# Auth.net
KiCad netlist of a schematic drawn in Altium Designer
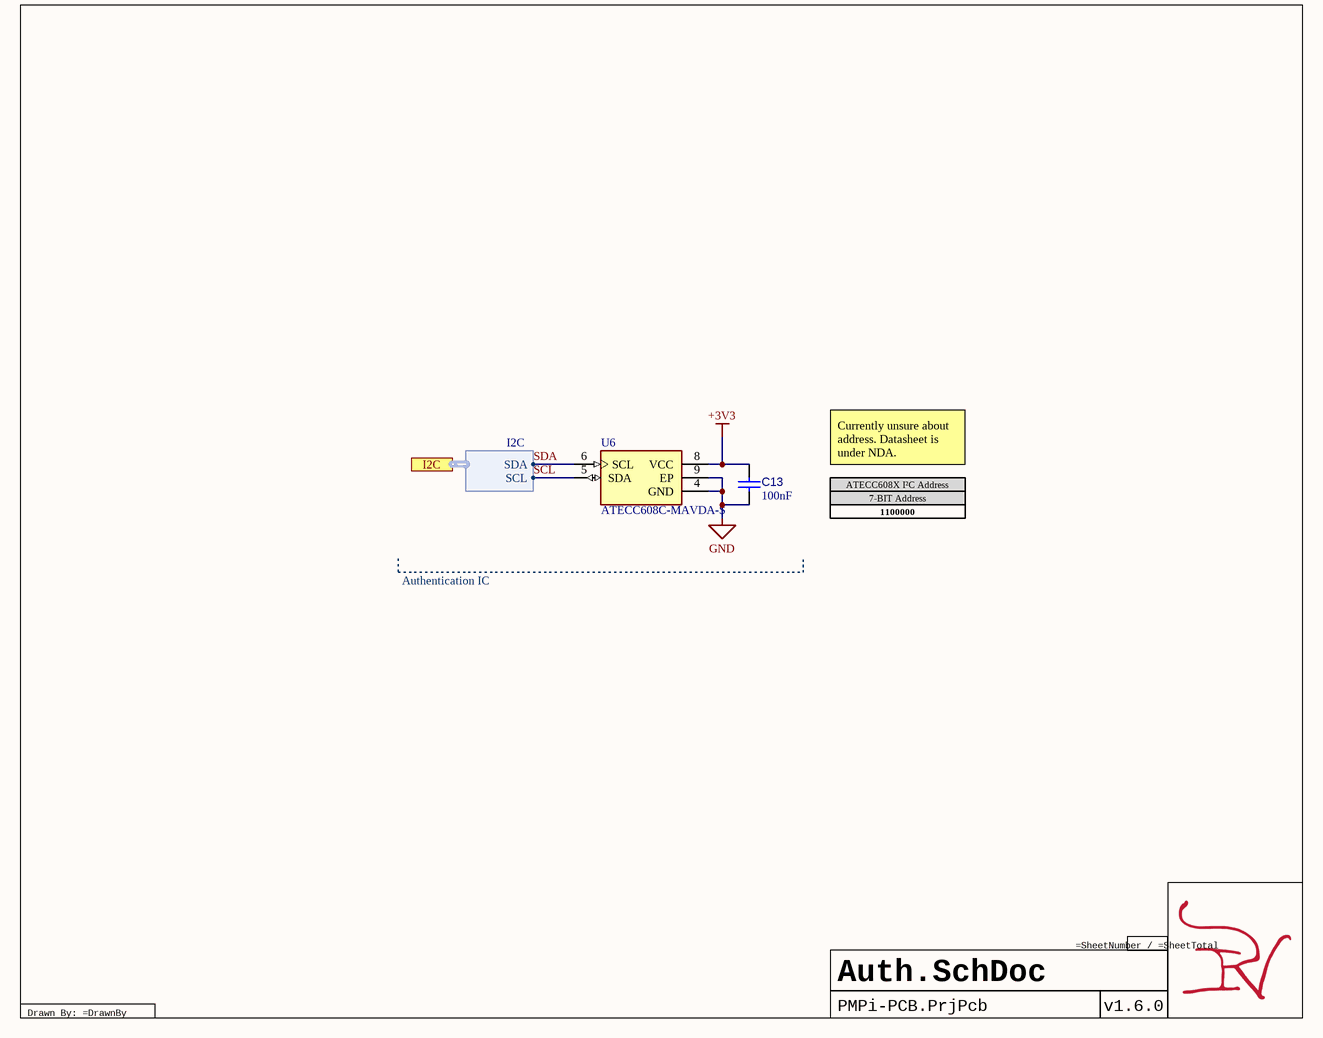
[diagram p0: Auth.SchDoc]

(export (version "E")
  (design (tool "Eeschema 10.0.6"))
  (components
    (comp (ref "C13")
      (value "100nF")
      (footprint "CAP 0402_1005")
      (fields (field (name "TOLERANCE") "10%") (field (name "Comment") "CAP-NP-2"))
      (libsource (lib "IIT Motorsports") (part "CAP-NP-2"))
    )
    (comp (ref "U6")
      (value "ATECC608C-MAVDA-S")
      (footprint "FP-C04-21355-Q4B-MFG")
      (description "ECC/ECDH, 100C, I2C, small 3K reel UDFN")
      (libsource (lib "IIT Motorsports") (part "bc8b69ea26d93e04a22732094f4cc99"))
    )
  )
  (nets
    (net (code "2") (name "+3V3") (class "Default")
      (node (ref "C13") (pin "1") (pinfunction "1_1") (pintype "passive"))
      (node (ref "U6") (pin "8") (pinfunction "VCC_8") (pintype "power_in"))
    )
    (net (code "3") (name "/SCL") (class "Default")
      (node (ref "U6") (pin "5") (pinfunction "SDA_5") (pintype "bidirectional"))
    )
    (net (code "4") (name "/SDA") (class "Default")
      (node (ref "U6") (pin "6") (pinfunction "SCL_6") (pintype "input"))
    )
    (net (code "6") (name "GND") (class "Default")
      (node (ref "C13") (pin "2") (pinfunction "2_2") (pintype "passive"))
      (node (ref "U6") (pin "4") (pinfunction "GND_4") (pintype "power_in"))
      (node (ref "U6") (pin "9") (pinfunction "EP_9") (pintype "power_in"))
    )
  )
)
